# GZ7_1_x-REMOT.net
KiCad netlist of a schematic drawn in Altium Designer
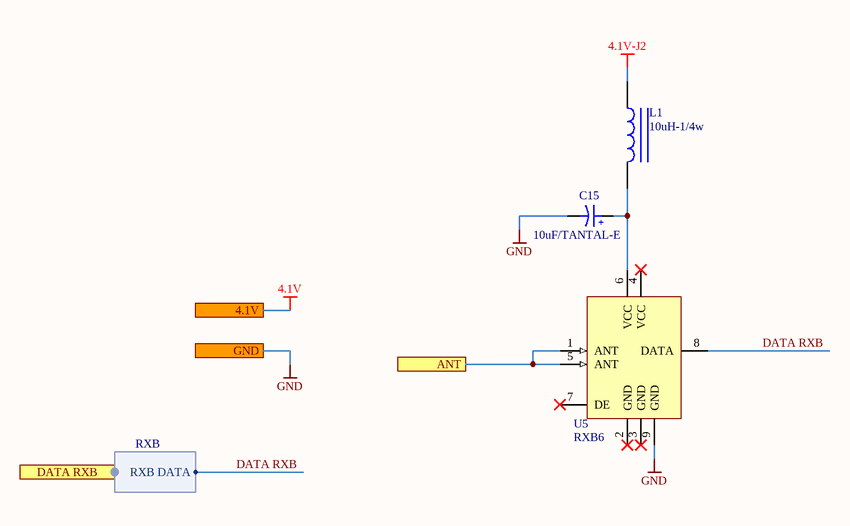
[diagram p0: GZ7_1_x-REMOT.SchDoc]

(export (version "E")
  (design (tool "Eeschema 10.0.6"))
  (components
    (comp (ref "C15")
      (value "10uF/TANTAL-E")
      (footprint "C_TN_3528")
      (description "Cap electrolitic radial")
      (fields (field (name "DESIGNER") "Abbas Basereh"))
      (libsource (lib "Altium") (part "Cap electrolitic radial 10x21"))
    )
    (comp (ref "L1")
      (value "10uH-1/4w")
      (footprint "Resistor_0.25w-0.4")
      (description "INDUCTOR 1/4w")
      (libsource (lib "*") (part "INDUCTOR IRON"))
    )
    (comp (ref "U5") (value "RXB6") (footprint "RXB_6") (libsource (lib "Ebrahim") (part "RXB6")))
  )
  (nets
    (net (code "2") (name "/ANT") (class "Default")
      (node (ref "U5") (pin "1") (pinfunction "ANT_1") (pintype "input"))
      (node (ref "U5") (pin "5") (pinfunction "ANT_5") (pintype "input"))
    )
    (net (code "3") (name "/DATA RXB") (class "Default")
      (node (ref "U5") (pin "8") (pinfunction "DATA_8") (pintype "passive"))
    )
    (net (code "6") (name "4.1V-J2") (class "Default")
      (node (ref "L1") (pin "1") (pinfunction "1_1") (pintype "passive"))
    )
    (net (code "7") (name "GND") (class "Default")
      (node (ref "C15") (pin "2") (pinfunction "2_2") (pintype "passive"))
      (node (ref "U5") (pin "9") (pinfunction "GND_9") (pintype "power_in"))
    )
    (net (code "8") (name "Net-(C15-Pad1)") (class "Default")
      (node (ref "C15") (pin "1") (pinfunction "1_1") (pintype "passive"))
      (node (ref "L1") (pin "2") (pinfunction "2_2") (pintype "passive"))
      (node (ref "U5") (pin "6") (pinfunction "VCC_6") (pintype "power_in"))
    )
    (net (code "9") (name "unconnected-(U5-DE-Pad7)") (class "Default")
      (node (ref "U5") (pin "7") (pinfunction "DE_7") (pintype "passive+no_connect"))
    )
    (net (code "10") (name "unconnected-(U5-GND-Pad2)") (class "Default")
      (node (ref "U5") (pin "2") (pinfunction "GND_2") (pintype "power_in+no_connect"))
    )
    (net (code "11") (name "unconnected-(U5-GND-Pad3)") (class "Default")
      (node (ref "U5") (pin "3") (pinfunction "GND_3") (pintype "power_in+no_connect"))
    )
    (net (code "12") (name "unconnected-(U5-VCC-Pad4)") (class "Default")
      (node (ref "U5") (pin "4") (pinfunction "VCC_4") (pintype "power_in+no_connect"))
    )
  )
)
